# MCU.net
KiCad netlist of a schematic drawn in Altium Designer
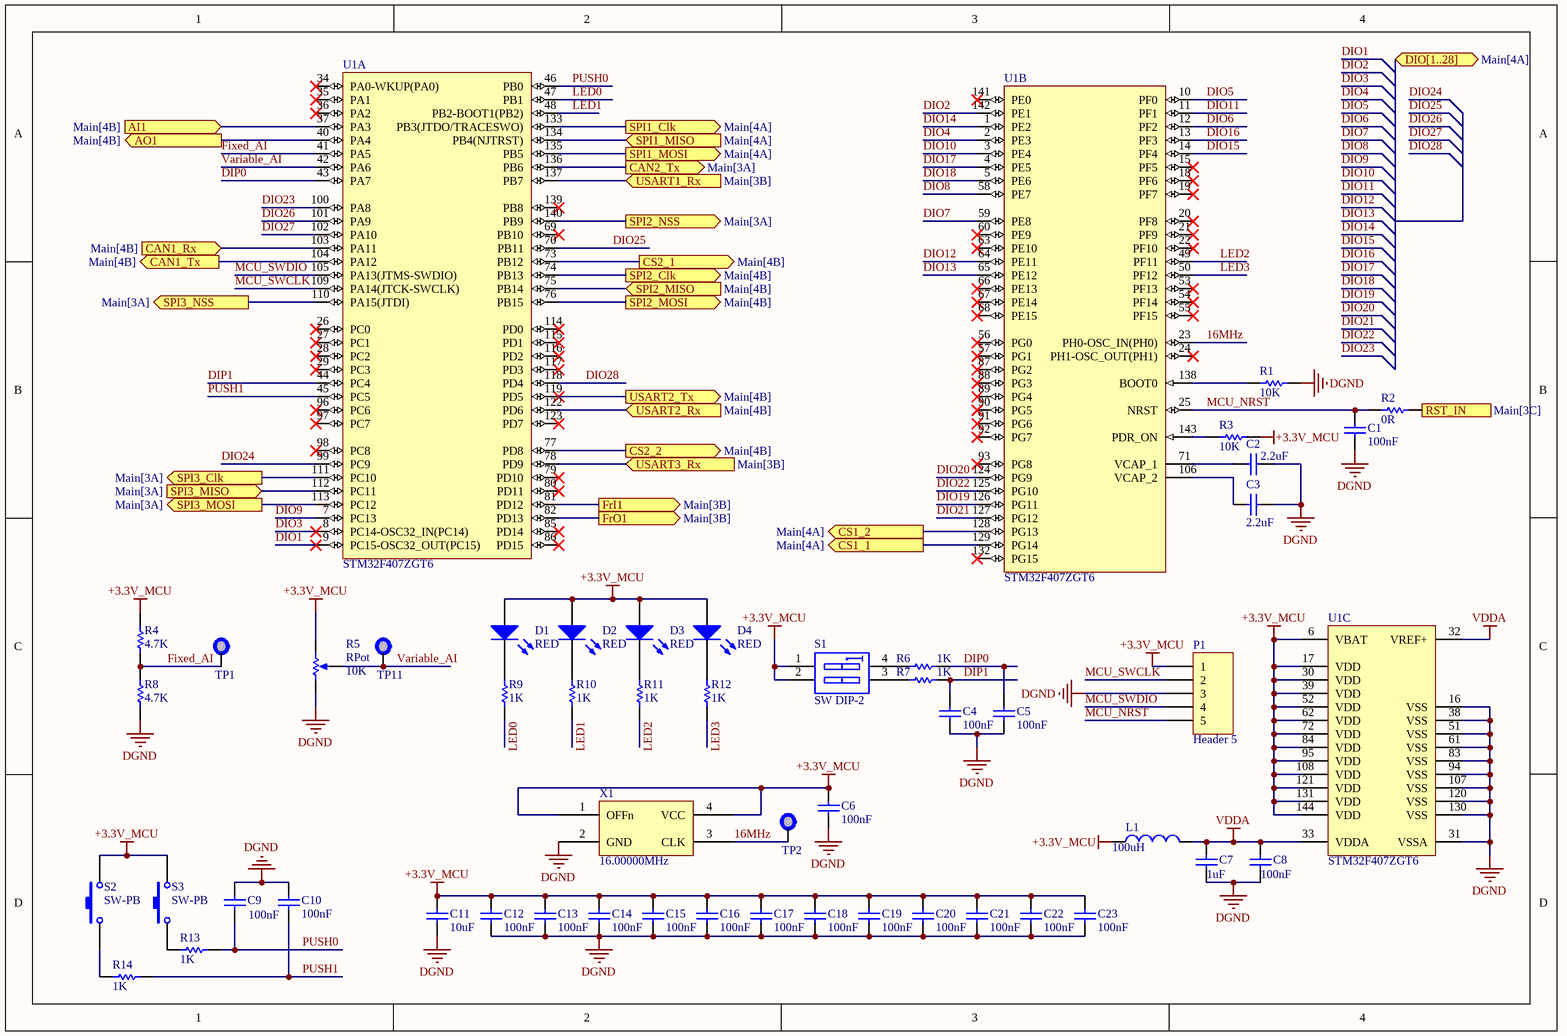
[diagram p0: MCU.SchDoc]

(export (version "E")
  (design (tool "Eeschema 10.0.6"))
  (components
    (comp (ref "C1")
      (value "100nF")
      (footprint "0603c")
      (description "LOW ESR")
      (fields (field (name "PUBLISHER") "Altium Limited"))
      (libsource (lib "Miscellaneous Devices") (part "Cap"))
    )
    (comp (ref "C2")
      (value "2.2uF")
      (footprint "0805C")
      (description "LOW ESR")
      (fields (field (name "PUBLISHER") "Altium Limited"))
      (libsource (lib "Miscellaneous Devices") (part "Cap"))
    )
    (comp (ref "C3")
      (value "2.2uF")
      (footprint "0805C")
      (description "LOW ESR")
      (fields (field (name "PUBLISHER") "Altium Limited"))
      (libsource (lib "Miscellaneous Devices") (part "Cap"))
    )
    (comp (ref "C4")
      (value "100nF")
      (footprint "0603c")
      (description "LOW ESR")
      (fields (field (name "PUBLISHER") "Altium Limited"))
      (libsource (lib "Miscellaneous Devices") (part "Cap"))
    )
    (comp (ref "C5")
      (value "100nF")
      (footprint "0603c")
      (description "LOW ESR")
      (fields (field (name "PUBLISHER") "Altium Limited"))
      (libsource (lib "Miscellaneous Devices") (part "Cap"))
    )
    (comp (ref "C6")
      (value "100nF")
      (footprint "0603C")
      (description "LOW ESR")
      (fields (field (name "PUBLISHER") "Altium Limited"))
      (libsource (lib "Miscellaneous Devices") (part "Cap"))
    )
    (comp (ref "C7")
      (value "1uF")
      (footprint "0805C")
      (description "LOW ESR")
      (fields (field (name "PUBLISHER") "Altium Limited"))
      (libsource (lib "Miscellaneous Devices") (part "Cap"))
    )
    (comp (ref "C8")
      (value "100nF")
      (footprint "0603C")
      (description "LOW ESR")
      (fields (field (name "PUBLISHER") "Altium Limited"))
      (libsource (lib "Miscellaneous Devices") (part "Cap"))
    )
    (comp (ref "C9")
      (value "100nF")
      (footprint "0603c")
      (description "LOW ESR")
      (fields (field (name "PUBLISHER") "Altium Limited"))
      (libsource (lib "Miscellaneous Devices") (part "Cap"))
    )
    (comp (ref "C10")
      (value "100nF")
      (footprint "0603c")
      (description "LOW ESR")
      (fields (field (name "PUBLISHER") "Altium Limited"))
      (libsource (lib "Miscellaneous Devices") (part "Cap"))
    )
    (comp (ref "C11")
      (value "10uF")
      (footprint "1206C")
      (description "LOW ESR")
      (fields (field (name "Comment") "10uf/50V") (field (name "PUBLISHER") "Altium Limited"))
      (libsource (lib "Miscellaneous Devices") (part "Cap"))
    )
    (comp (ref "C12")
      (value "100nF")
      (footprint "0603c")
      (description "LOW ESR")
      (fields (field (name "PUBLISHER") "Altium Limited"))
      (libsource (lib "Miscellaneous Devices") (part "Cap"))
    )
    (comp (ref "C13")
      (value "100nF")
      (footprint "0603c")
      (description "LOW ESR")
      (fields (field (name "PUBLISHER") "Altium Limited"))
      (libsource (lib "Miscellaneous Devices") (part "Cap"))
    )
    (comp (ref "C14")
      (value "100nF")
      (footprint "0603c")
      (description "LOW ESR")
      (fields (field (name "PUBLISHER") "Altium Limited"))
      (libsource (lib "Miscellaneous Devices") (part "Cap"))
    )
    (comp (ref "C15")
      (value "100nF")
      (footprint "0603c")
      (description "LOW ESR")
      (fields (field (name "PUBLISHER") "Altium Limited"))
      (libsource (lib "Miscellaneous Devices") (part "Cap"))
    )
    (comp (ref "C16")
      (value "100nF")
      (footprint "0603c")
      (description "LOW ESR")
      (fields (field (name "PUBLISHER") "Altium Limited"))
      (libsource (lib "Miscellaneous Devices") (part "Cap"))
    )
    (comp (ref "C17")
      (value "100nF")
      (footprint "0603c")
      (description "LOW ESR")
      (fields (field (name "PUBLISHER") "Altium Limited"))
      (libsource (lib "Miscellaneous Devices") (part "Cap"))
    )
    (comp (ref "C18")
      (value "100nF")
      (footprint "0603c")
      (description "LOW ESR")
      (fields (field (name "PUBLISHER") "Altium Limited"))
      (libsource (lib "Miscellaneous Devices") (part "Cap"))
    )
    (comp (ref "C19")
      (value "100nF")
      (footprint "0603c")
      (description "LOW ESR")
      (fields (field (name "PUBLISHER") "Altium Limited"))
      (libsource (lib "Miscellaneous Devices") (part "Cap"))
    )
    (comp (ref "C20")
      (value "100nF")
      (footprint "0603c")
      (description "LOW ESR")
      (fields (field (name "PUBLISHER") "Altium Limited"))
      (libsource (lib "Miscellaneous Devices") (part "Cap"))
    )
    (comp (ref "C21")
      (value "100nF")
      (footprint "0603c")
      (description "LOW ESR")
      (fields (field (name "PUBLISHER") "Altium Limited"))
      (libsource (lib "Miscellaneous Devices") (part "Cap"))
    )
    (comp (ref "C22")
      (value "100nF")
      (footprint "0603c")
      (description "LOW ESR")
      (fields (field (name "PUBLISHER") "Altium Limited"))
      (libsource (lib "Miscellaneous Devices") (part "Cap"))
    )
    (comp (ref "C23")
      (value "100nF")
      (footprint "0603c")
      (description "LOW ESR")
      (fields (field (name "PUBLISHER") "Altium Limited"))
      (libsource (lib "Miscellaneous Devices") (part "Cap"))
    )
    (comp (ref "D1")
      (value "RED")
      (footprint "0805LED")
      (fields (field (name "PUBLISHER") "Altium Limited"))
      (libsource (lib "Miscellaneous Devices") (part "LED0"))
    )
    (comp (ref "D2")
      (value "RED")
      (footprint "0805LED")
      (fields (field (name "PUBLISHER") "Altium Limited"))
      (libsource (lib "Miscellaneous Devices") (part "LED0"))
    )
    (comp (ref "D3")
      (value "RED")
      (footprint "0805LED")
      (fields (field (name "PUBLISHER") "Altium Limited"))
      (libsource (lib "Miscellaneous Devices") (part "LED0"))
    )
    (comp (ref "D4")
      (value "RED")
      (footprint "0805LED")
      (fields (field (name "PUBLISHER") "Altium Limited"))
      (libsource (lib "Miscellaneous Devices") (part "LED0"))
    )
    (comp (ref "L1")
      (value "100uH")
      (footprint "0805FB")
      (description "Inductor")
      (fields (field (name "PUBLISHER") "Altium Limited"))
      (libsource (lib "Miscellaneous Devices") (part "Inductor"))
    )
    (comp (ref "P1")
      (value "Header 5")
      (footprint "HDR1X5")
      (description "Header, 5-Pin")
      (fields (field (name "PUBLISHER") "Altium Limited"))
      (libsource (lib "Miscellaneous Connectors") (part "Header 5"))
    )
    (comp (ref "R1")
      (value "10K")
      (footprint "0805")
      (description "Resistor")
      (fields (field (name "PUBLISHER") "Altium Limited"))
      (libsource (lib "Miscellaneous Devices") (part "Res1"))
    )
    (comp (ref "R2")
      (value "0R")
      (footprint "0805")
      (description "Resistor")
      (fields (field (name "PUBLISHER") "Altium Limited"))
      (libsource (lib "Miscellaneous Devices") (part "Res1"))
    )
    (comp (ref "R3")
      (value "10K")
      (footprint "0805")
      (description "Resistor")
      (fields (field (name "PUBLISHER") "Altium Limited"))
      (libsource (lib "Miscellaneous Devices") (part "Res1"))
    )
    (comp (ref "R4")
      (value "4.7K")
      (footprint "0805")
      (description "Resistor")
      (fields (field (name "PUBLISHER") "Altium Limited"))
      (libsource (lib "Miscellaneous Devices") (part "Res1"))
    )
    (comp (ref "R5")
      (value "RPot")
      (footprint "POT-MULTITURN")
      (description "MultiTurn")
      (fields (field (name "ALTIUM_VALUE") "10K") (field (name "PUBLISHER") "Altium Limited"))
      (libsource (lib "Miscellaneous Devices") (part "RPot"))
    )
    (comp (ref "R6")
      (value "1K")
      (footprint "0805")
      (description "Resistor")
      (fields (field (name "PUBLISHER") "Altium Limited"))
      (libsource (lib "Miscellaneous Devices") (part "Res1"))
    )
    (comp (ref "R7")
      (value "1K")
      (footprint "0805")
      (description "Resistor")
      (fields (field (name "PUBLISHER") "Altium Limited"))
      (libsource (lib "Miscellaneous Devices") (part "Res1"))
    )
    (comp (ref "R8")
      (value "4.7K")
      (footprint "0805")
      (description "Resistor")
      (fields (field (name "PUBLISHER") "Altium Limited"))
      (libsource (lib "Miscellaneous Devices") (part "Res1"))
    )
    (comp (ref "R9")
      (value "1K")
      (footprint "0805")
      (description "Resistor")
      (fields (field (name "PUBLISHER") "Altium Limited"))
      (libsource (lib "Miscellaneous Devices") (part "Res1"))
    )
    (comp (ref "R10")
      (value "1K")
      (footprint "0805")
      (description "Resistor")
      (fields (field (name "PUBLISHER") "Altium Limited"))
      (libsource (lib "Miscellaneous Devices") (part "Res1"))
    )
    (comp (ref "R11")
      (value "1K")
      (footprint "0805")
      (description "Resistor")
      (fields (field (name "PUBLISHER") "Altium Limited"))
      (libsource (lib "Miscellaneous Devices") (part "Res1"))
    )
    (comp (ref "R12")
      (value "1K")
      (footprint "0805")
      (description "Resistor")
      (fields (field (name "PUBLISHER") "Altium Limited"))
      (libsource (lib "Miscellaneous Devices") (part "Res1"))
    )
    (comp (ref "R13")
      (value "1K")
      (footprint "0805")
      (description "Resistor")
      (fields (field (name "PUBLISHER") "Altium Limited"))
      (libsource (lib "Miscellaneous Devices") (part "Res1"))
    )
    (comp (ref "R14")
      (value "1K")
      (footprint "0805")
      (description "Resistor")
      (fields (field (name "PUBLISHER") "Altium Limited"))
      (libsource (lib "Miscellaneous Devices") (part "Res1"))
    )
    (comp (ref "S1")
      (value "SW DIP-2")
      (footprint "DIP-4")
      (description "DIP Switch, 2 Position, SPST")
      (fields (field (name "PUBLISHER") "Altium Limited"))
      (libsource (lib "Miscellaneous Devices") (part "SW DIP-2"))
    )
    (comp (ref "S2")
      (value "SW-PB")
      (footprint "PUSHBUTTON-SMD")
      (description "Switch")
      (fields (field (name "PUBLISHER") "Altium Limited"))
      (libsource (lib "Miscellaneous Devices") (part "SW-PB"))
    )
    (comp (ref "S3")
      (value "SW-PB")
      (footprint "PUSHBUTTON-SMD")
      (description "Switch")
      (fields (field (name "PUBLISHER") "Altium Limited"))
      (libsource (lib "Miscellaneous Devices") (part "SW-PB"))
    )
    (comp (ref "TP1") (value "TestPoint") (footprint "TP") (libsource (lib "SchlibV0.1") (part "TestPoint")))
    (comp (ref "TP2") (value "TestPoint") (footprint "TP") (libsource (lib "SchlibV0.1") (part "TestPoint")))
    (comp (ref "TP11") (value "TestPoint") (footprint "TP") (libsource (lib "SchlibV0.1") (part "TestPoint")))
    (comp (ref "U1")
      (value "STM32F407ZGT6")
      (footprint "STM-LQFP144_N")
      (fields (field (name "MANUFACTURER") "STMicroelectronics"))
      (libsource (lib "STMicroelectronics STM32 F4") (part "STM32F407ZGT6"))
    )
    (comp (ref "X1")
      (value "16.00000MHz")
      (footprint "OSC-SMT")
      (fields (field (name "Comment") "SG-8018CB 16.000000 MHZ TJHPA"))
      (libsource (lib "TMS320F2812-PGF") (part "Oscillator"))
    )
  )
  (nets
    (net (code "1") (name "+3.3V_MCU") (class "Default")
      (node (ref "C11") (pin "2") (pinfunction "2_2") (pintype "passive"))
      (node (ref "C12") (pin "1") (pinfunction "1_1") (pintype "passive"))
      (node (ref "C13") (pin "1") (pinfunction "1_1") (pintype "passive"))
      (node (ref "C14") (pin "1") (pinfunction "1_1") (pintype "passive"))
      (node (ref "C15") (pin "1") (pinfunction "1_1") (pintype "passive"))
      (node (ref "C16") (pin "1") (pinfunction "1_1") (pintype "passive"))
      (node (ref "C17") (pin "1") (pinfunction "1_1") (pintype "passive"))
      (node (ref "C18") (pin "1") (pinfunction "1_1") (pintype "passive"))
      (node (ref "C19") (pin "1") (pinfunction "1_1") (pintype "passive"))
      (node (ref "C20") (pin "1") (pinfunction "1_1") (pintype "passive"))
      (node (ref "C21") (pin "1") (pinfunction "1_1") (pintype "passive"))
      (node (ref "C22") (pin "1") (pinfunction "1_1") (pintype "passive"))
      (node (ref "C23") (pin "1") (pinfunction "1_1") (pintype "passive"))
      (node (ref "C6") (pin "1") (pinfunction "1_1") (pintype "passive"))
      (node (ref "D1") (pin "1") (pinfunction "A_1") (pintype "passive"))
      (node (ref "D2") (pin "1") (pinfunction "A_1") (pintype "passive"))
      (node (ref "D3") (pin "1") (pinfunction "A_1") (pintype "passive"))
      (node (ref "D4") (pin "1") (pinfunction "A_1") (pintype "passive"))
      (node (ref "L1") (pin "1") (pinfunction "1_1") (pintype "passive"))
      (node (ref "P1") (pin "1") (pinfunction "1_1") (pintype "passive"))
      (node (ref "R3") (pin "1") (pinfunction "1_1") (pintype "passive"))
      (node (ref "R4") (pin "2") (pinfunction "2_2") (pintype "passive"))
      (node (ref "R5") (pin "3") (pinfunction "BOT_3") (pintype "passive"))
      (node (ref "S1") (pin "1") (pinfunction "A1_1") (pintype "passive"))
      (node (ref "S1") (pin "2") (pinfunction "A2_2") (pintype "passive"))
      (node (ref "S2") (pin "2") (pinfunction "2_2") (pintype "passive"))
      (node (ref "S3") (pin "2") (pinfunction "2_2") (pintype "passive"))
      (node (ref "U1") (pin "108") (pinfunction "VDD_108") (pintype "power_in"))
      (node (ref "U1") (pin "121") (pinfunction "VDD_121") (pintype "power_in"))
      (node (ref "U1") (pin "131") (pinfunction "VDD_131") (pintype "power_in"))
      (node (ref "U1") (pin "144") (pinfunction "VDD_144") (pintype "power_in"))
      (node (ref "U1") (pin "17") (pinfunction "VDD_17") (pintype "power_in"))
      (node (ref "U1") (pin "30") (pinfunction "VDD_30") (pintype "power_in"))
      (node (ref "U1") (pin "39") (pinfunction "VDD_39") (pintype "power_in"))
      (node (ref "U1") (pin "52") (pinfunction "VDD_52") (pintype "power_in"))
      (node (ref "U1") (pin "6") (pinfunction "VBAT_6") (pintype "power_in"))
      (node (ref "U1") (pin "62") (pinfunction "VDD_62") (pintype "power_in"))
      (node (ref "U1") (pin "72") (pinfunction "VDD_72") (pintype "power_in"))
      (node (ref "U1") (pin "84") (pinfunction "VDD_84") (pintype "power_in"))
      (node (ref "U1") (pin "95") (pinfunction "VDD_95") (pintype "power_in"))
      (node (ref "X1") (pin "1") (pinfunction "OFFn_1") (pintype "passive"))
      (node (ref "X1") (pin "4") (pinfunction "VCC_4") (pintype "passive"))
    )
    (net (code "2") (name "/16MHz") (class "Default")
      (node (ref "TP2") (pin "1") (pintype "passive"))
      (node (ref "U1") (pin "23") (pinfunction "PH0-OSC_IN(PH0)_23") (pintype "bidirectional"))
      (node (ref "X1") (pin "3") (pinfunction "CLK_3") (pintype "passive"))
    )
    (net (code "3") (name "/AI1") (class "Default")
      (node (ref "U1") (pin "37") (pinfunction "PA3_37") (pintype "bidirectional"))
    )
    (net (code "4") (name "/AO1") (class "Default")
      (node (ref "U1") (pin "40") (pinfunction "PA4_40") (pintype "bidirectional"))
    )
    (net (code "5") (name "/CAN1_Rx") (class "Default")
      (node (ref "U1") (pin "103") (pinfunction "PA11_103") (pintype "bidirectional"))
    )
    (net (code "6") (name "/CAN1_Tx") (class "Default")
      (node (ref "U1") (pin "104") (pinfunction "PA12_104") (pintype "bidirectional"))
    )
    (net (code "7") (name "/CAN2_Tx") (class "Default")
      (node (ref "U1") (pin "136") (pinfunction "PB6_136") (pintype "bidirectional"))
    )
    (net (code "8") (name "/CS1_1") (class "Default")
      (node (ref "U1") (pin "129") (pinfunction "PG14_129") (pintype "bidirectional"))
    )
    (net (code "9") (name "/CS1_2") (class "Default")
      (node (ref "U1") (pin "128") (pinfunction "PG13_128") (pintype "bidirectional"))
    )
    (net (code "10") (name "/CS2_1") (class "Default")
      (node (ref "U1") (pin "73") (pinfunction "PB12_73") (pintype "bidirectional"))
    )
    (net (code "11") (name "/CS2_2") (class "Default")
      (node (ref "U1") (pin "77") (pinfunction "PD8_77") (pintype "bidirectional"))
    )
    (net (code "12") (name "/DIO1") (class "Default")
      (node (ref "U1") (pin "9") (pinfunction "PC15-OSC32_OUT(PC15)_9") (pintype "bidirectional+no_connect"))
    )
    (net (code "13") (name "/DIO2") (class "Default")
      (node (ref "U1") (pin "142") (pinfunction "PE1_142") (pintype "bidirectional"))
    )
    (net (code "14") (name "/DIO3") (class "Default")
      (node (ref "U1") (pin "8") (pinfunction "PC14-OSC32_IN(PC14)_8") (pintype "bidirectional+no_connect"))
    )
    (net (code "15") (name "/DIO4") (class "Default")
      (node (ref "U1") (pin "2") (pinfunction "PE3_2") (pintype "bidirectional"))
    )
    (net (code "16") (name "/DIO5") (class "Default")
      (node (ref "U1") (pin "10") (pinfunction "PF0_10") (pintype "bidirectional"))
    )
    (net (code "17") (name "/DIO6") (class "Default")
      (node (ref "U1") (pin "12") (pinfunction "PF2_12") (pintype "bidirectional"))
    )
    (net (code "18") (name "/DIO7") (class "Default")
      (node (ref "U1") (pin "59") (pinfunction "PE8_59") (pintype "bidirectional"))
    )
    (net (code "19") (name "/DIO8") (class "Default")
      (node (ref "U1") (pin "58") (pinfunction "PE7_58") (pintype "bidirectional"))
    )
    (net (code "20") (name "/DIO9") (class "Default")
      (node (ref "U1") (pin "7") (pinfunction "PC13_7") (pintype "bidirectional"))
    )
    (net (code "21") (name "/DIO10") (class "Default")
      (node (ref "U1") (pin "3") (pinfunction "PE4_3") (pintype "bidirectional"))
    )
    (net (code "22") (name "/DIO11") (class "Default")
      (node (ref "U1") (pin "11") (pinfunction "PF1_11") (pintype "bidirectional"))
    )
    (net (code "23") (name "/DIO12") (class "Default")
      (node (ref "U1") (pin "64") (pinfunction "PE11_64") (pintype "bidirectional"))
    )
    (net (code "24") (name "/DIO13") (class "Default")
      (node (ref "U1") (pin "65") (pinfunction "PE12_65") (pintype "bidirectional"))
    )
    (net (code "25") (name "/DIO14") (class "Default")
      (node (ref "U1") (pin "1") (pinfunction "PE2_1") (pintype "bidirectional"))
    )
    (net (code "26") (name "/DIO15") (class "Default")
      (node (ref "U1") (pin "14") (pinfunction "PF4_14") (pintype "bidirectional"))
    )
    (net (code "27") (name "/DIO16") (class "Default")
      (node (ref "U1") (pin "13") (pinfunction "PF3_13") (pintype "bidirectional"))
    )
    (net (code "28") (name "/DIO17") (class "Default")
      (node (ref "U1") (pin "4") (pinfunction "PE5_4") (pintype "bidirectional"))
    )
    (net (code "29") (name "/DIO18") (class "Default")
      (node (ref "U1") (pin "5") (pinfunction "PE6_5") (pintype "bidirectional"))
    )
    (net (code "30") (name "/DIO19") (class "Default")
      (node (ref "U1") (pin "126") (pinfunction "PG11_126") (pintype "bidirectional"))
    )
    (net (code "31") (name "/DIO20") (class "Default")
      (node (ref "U1") (pin "124") (pinfunction "PG9_124") (pintype "bidirectional"))
    )
    (net (code "32") (name "/DIO21") (class "Default")
      (node (ref "U1") (pin "127") (pinfunction "PG12_127") (pintype "bidirectional"))
    )
    (net (code "33") (name "/DIO22") (class "Default")
      (node (ref "U1") (pin "125") (pinfunction "PG10_125") (pintype "bidirectional"))
    )
    (net (code "34") (name "/DIO23") (class "Default")
      (node (ref "U1") (pin "100") (pinfunction "PA8_100") (pintype "bidirectional"))
    )
    (net (code "35") (name "/DIO24") (class "Default")
      (node (ref "U1") (pin "99") (pinfunction "PC9_99") (pintype "bidirectional"))
    )
    (net (code "36") (name "/DIO25") (class "Default")
      (node (ref "U1") (pin "70") (pinfunction "PB11_70") (pintype "bidirectional"))
    )
    (net (code "37") (name "/DIO26") (class "Default")
      (node (ref "U1") (pin "101") (pinfunction "PA9_101") (pintype "bidirectional"))
    )
    (net (code "38") (name "/DIO27") (class "Default")
      (node (ref "U1") (pin "102") (pinfunction "PA10_102") (pintype "bidirectional"))
    )
    (net (code "39") (name "/DIO28") (class "Default")
      (node (ref "U1") (pin "118") (pinfunction "PD4_118") (pintype "bidirectional"))
    )
    (net (code "41") (name "/DIP0") (class "Default")
      (node (ref "C5") (pin "1") (pinfunction "1_1") (pintype "passive"))
      (node (ref "R6") (pin "2") (pinfunction "2_2") (pintype "passive"))
      (node (ref "U1") (pin "43") (pinfunction "PA7_43") (pintype "bidirectional"))
    )
    (net (code "42") (name "/DIP1") (class "Default")
      (node (ref "C4") (pin "1") (pinfunction "1_1") (pintype "passive"))
      (node (ref "R7") (pin "2") (pinfunction "2_2") (pintype "passive"))
      (node (ref "U1") (pin "44") (pinfunction "PC4_44") (pintype "bidirectional"))
    )
    (net (code "43") (name "/Fixed_AI") (class "Default")
      (node (ref "R4") (pin "1") (pinfunction "1_1") (pintype "passive"))
      (node (ref "R8") (pin "2") (pinfunction "2_2") (pintype "passive"))
      (node (ref "TP1") (pin "1") (pintype "passive"))
      (node (ref "U1") (pin "41") (pinfunction "PA5_41") (pintype "bidirectional"))
    )
    (net (code "44") (name "/FrI1") (class "Default")
      (node (ref "U1") (pin "81") (pinfunction "PD12_81") (pintype "bidirectional"))
    )
    (net (code "45") (name "/FrO1") (class "Default")
      (node (ref "U1") (pin "82") (pinfunction "PD13_82") (pintype "bidirectional"))
    )
    (net (code "46") (name "/LED0") (class "Default")
      (node (ref "R9") (pin "1") (pinfunction "1_1") (pintype "passive"))
      (node (ref "U1") (pin "47") (pinfunction "PB1_47") (pintype "bidirectional"))
    )
    (net (code "47") (name "/LED1") (class "Default")
      (node (ref "R10") (pin "1") (pinfunction "1_1") (pintype "passive"))
      (node (ref "U1") (pin "48") (pinfunction "PB2-BOOT1(PB2)_48") (pintype "bidirectional"))
    )
    (net (code "48") (name "/LED2") (class "Default")
      (node (ref "R11") (pin "1") (pinfunction "1_1") (pintype "passive"))
      (node (ref "U1") (pin "49") (pinfunction "PF11_49") (pintype "bidirectional"))
    )
    (net (code "49") (name "/LED3") (class "Default")
      (node (ref "R12") (pin "1") (pinfunction "1_1") (pintype "passive"))
      (node (ref "U1") (pin "50") (pinfunction "PF12_50") (pintype "bidirectional"))
    )
    (net (code "50") (name "/MCU_NRST") (class "Default")
      (node (ref "C1") (pin "1") (pinfunction "1_1") (pintype "passive"))
      (node (ref "P1") (pin "5") (pinfunction "5_5") (pintype "passive"))
      (node (ref "R2") (pin "2") (pinfunction "2_2") (pintype "passive"))
      (node (ref "U1") (pin "25") (pinfunction "NRST_25") (pintype "bidirectional"))
    )
    (net (code "51") (name "/MCU_SWCLK") (class "Default")
      (node (ref "P1") (pin "2") (pinfunction "2_2") (pintype "passive"))
      (node (ref "U1") (pin "109") (pinfunction "PA14(JTCK-SWCLK)_109") (pintype "bidirectional"))
    )
    (net (code "52") (name "/MCU_SWDIO") (class "Default")
      (node (ref "P1") (pin "4") (pinfunction "4_4") (pintype "passive"))
      (node (ref "U1") (pin "105") (pinfunction "PA13(JTMS-SWDIO)_105") (pintype "bidirectional"))
    )
    (net (code "53") (name "/PUSH0") (class "Default")
      (node (ref "C9") (pin "2") (pinfunction "2_2") (pintype "passive"))
      (node (ref "R13") (pin "2") (pinfunction "2_2") (pintype "passive"))
      (node (ref "U1") (pin "46") (pinfunction "PB0_46") (pintype "bidirectional"))
    )
    (net (code "54") (name "/PUSH1") (class "Default")
      (node (ref "C10") (pin "2") (pinfunction "2_2") (pintype "passive"))
      (node (ref "R14") (pin "1") (pinfunction "1_1") (pintype "passive"))
      (node (ref "U1") (pin "45") (pinfunction "PC5_45") (pintype "bidirectional"))
    )
    (net (code "55") (name "/RST_IN") (class "Default")
      (node (ref "R2") (pin "1") (pinfunction "1_1") (pintype "passive"))
    )
    (net (code "56") (name "/SPI1_Clk") (class "Default")
      (node (ref "U1") (pin "133") (pinfunction "PB3(JTDO/TRACESWO)_133") (pintype "bidirectional"))
    )
    (net (code "57") (name "/SPI1_MISO") (class "Default")
      (node (ref "U1") (pin "134") (pinfunction "PB4(NJTRST)_134") (pintype "bidirectional"))
    )
    (net (code "58") (name "/SPI1_MOSI") (class "Default")
      (node (ref "U1") (pin "135") (pinfunction "PB5_135") (pintype "bidirectional"))
    )
    (net (code "59") (name "/SPI2_Clk") (class "Default")
      (node (ref "U1") (pin "74") (pinfunction "PB13_74") (pintype "bidirectional"))
    )
    (net (code "60") (name "/SPI2_MISO") (class "Default")
      (node (ref "U1") (pin "75") (pinfunction "PB14_75") (pintype "bidirectional"))
    )
    (net (code "61") (name "/SPI2_MOSI") (class "Default")
      (node (ref "U1") (pin "76") (pinfunction "PB15_76") (pintype "bidirectional"))
    )
    (net (code "62") (name "/SPI2_NSS") (class "Default")
      (node (ref "U1") (pin "140") (pinfunction "PB9_140") (pintype "bidirectional"))
    )
    (net (code "63") (name "/SPI3_Clk") (class "Default")
      (node (ref "U1") (pin "111") (pinfunction "PC10_111") (pintype "bidirectional"))
    )
    (net (code "64") (name "/SPI3_MISO") (class "Default")
      (node (ref "U1") (pin "112") (pinfunction "PC11_112") (pintype "bidirectional"))
    )
    (net (code "65") (name "/SPI3_MOSI") (class "Default")
      (node (ref "U1") (pin "113") (pinfunction "PC12_113") (pintype "bidirectional"))
    )
    (net (code "66") (name "/SPI3_NSS") (class "Default")
      (node (ref "U1") (pin "110") (pinfunction "PA15(JTDI)_110") (pintype "bidirectional"))
    )
    (net (code "67") (name "/USART1_Rx") (class "Default")
      (node (ref "U1") (pin "137") (pinfunction "PB7_137") (pintype "bidirectional"))
    )
    (net (code "68") (name "/USART2_Rx") (class "Default")
      (node (ref "U1") (pin "122") (pinfunction "PD6_122") (pintype "bidirectional"))
    )
    (net (code "69") (name "/USART2_Tx") (class "Default")
      (node (ref "U1") (pin "119") (pinfunction "PD5_119") (pintype "bidirectional+no_connect"))
    )
    (net (code "70") (name "/USART3_Rx") (class "Default")
      (node (ref "U1") (pin "78") (pinfunction "PD9_78") (pintype "bidirectional"))
    )
    (net (code "71") (name "/Variable_AI") (class "Default")
      (node (ref "R5") (pin "2") (pinfunction "TAP_2") (pintype "passive"))
      (node (ref "TP11") (pin "1") (pintype "passive"))
      (node (ref "U1") (pin "42") (pinfunction "PA6_42") (pintype "bidirectional"))
    )
    (net (code "72") (name "DGND") (class "Default")
      (node (ref "C1") (pin "2") (pinfunction "2_2") (pintype "passive"))
      (node (ref "C10") (pin "1") (pinfunction "1_1") (pintype "passive"))
      (node (ref "C11") (pin "1") (pinfunction "1_1") (pintype "passive"))
      (node (ref "C12") (pin "2") (pinfunction "2_2") (pintype "passive"))
      (node (ref "C13") (pin "2") (pinfunction "2_2") (pintype "passive"))
      (node (ref "C14") (pin "2") (pinfunction "2_2") (pintype "passive"))
      (node (ref "C15") (pin "2") (pinfunction "2_2") (pintype "passive"))
      (node (ref "C16") (pin "2") (pinfunction "2_2") (pintype "passive"))
      (node (ref "C17") (pin "2") (pinfunction "2_2") (pintype "passive"))
      (node (ref "C18") (pin "2") (pinfunction "2_2") (pintype "passive"))
      (node (ref "C19") (pin "2") (pinfunction "2_2") (pintype "passive"))
      (node (ref "C2") (pin "2") (pinfunction "2_2") (pintype "passive"))
      (node (ref "C20") (pin "2") (pinfunction "2_2") (pintype "passive"))
      (node (ref "C21") (pin "2") (pinfunction "2_2") (pintype "passive"))
      (node (ref "C22") (pin "2") (pinfunction "2_2") (pintype "passive"))
      (node (ref "C23") (pin "2") (pinfunction "2_2") (pintype "passive"))
      (node (ref "C3") (pin "2") (pinfunction "2_2") (pintype "passive"))
      (node (ref "C4") (pin "2") (pinfunction "2_2") (pintype "passive"))
      (node (ref "C5") (pin "2") (pinfunction "2_2") (pintype "passive"))
      (node (ref "C6") (pin "2") (pinfunction "2_2") (pintype "passive"))
      (node (ref "C7") (pin "1") (pinfunction "1_1") (pintype "passive"))
      (node (ref "C8") (pin "1") (pinfunction "1_1") (pintype "passive"))
      (node (ref "C9") (pin "1") (pinfunction "1_1") (pintype "passive"))
      (node (ref "P1") (pin "3") (pinfunction "3_3") (pintype "passive"))
      (node (ref "R1") (pin "1") (pinfunction "1_1") (pintype "passive"))
      (node (ref "R5") (pin "1") (pinfunction "TOP_1") (pintype "passive"))
      (node (ref "R8") (pin "1") (pinfunction "1_1") (pintype "passive"))
      (node (ref "U1") (pin "107") (pinfunction "VSS_107") (pintype "power_in"))
      (node (ref "U1") (pin "120") (pinfunction "VSS_120") (pintype "power_in"))
      (node (ref "U1") (pin "130") (pinfunction "VSS_130") (pintype "power_in"))
      (node (ref "U1") (pin "16") (pinfunction "VSS_16") (pintype "power_in"))
      (node (ref "U1") (pin "31") (pinfunction "VSSA_31") (pintype "power_in"))
      (node (ref "U1") (pin "38") (pinfunction "VSS_38") (pintype "power_in"))
      (node (ref "U1") (pin "51") (pinfunction "VSS_51") (pintype "power_in"))
      (node (ref "U1") (pin "61") (pinfunction "VSS_61") (pintype "power_in"))
      (node (ref "U1") (pin "83") (pinfunction "VSS_83") (pintype "power_in"))
      (node (ref "U1") (pin "94") (pinfunction "VSS_94") (pintype "power_in"))
      (node (ref "X1") (pin "2") (pinfunction "GND_2") (pintype "passive"))
    )
    (net (code "73") (name "Net-(D1-K)") (class "Default")
      (node (ref "D1") (pin "2") (pinfunction "K_2") (pintype "passive"))
      (node (ref "R9") (pin "2") (pinfunction "2_2") (pintype "passive"))
    )
    (net (code "74") (name "Net-(D2-K)") (class "Default")
      (node (ref "D2") (pin "2") (pinfunction "K_2") (pintype "passive"))
      (node (ref "R10") (pin "2") (pinfunction "2_2") (pintype "passive"))
    )
    (net (code "75") (name "Net-(D3-K)") (class "Default")
      (node (ref "D3") (pin "2") (pinfunction "K_2") (pintype "passive"))
      (node (ref "R11") (pin "2") (pinfunction "2_2") (pintype "passive"))
    )
    (net (code "76") (name "Net-(D4-K)") (class "Default")
      (node (ref "D4") (pin "2") (pinfunction "K_2") (pintype "passive"))
      (node (ref "R12") (pin "2") (pinfunction "2_2") (pintype "passive"))
    )
    (net (code "77") (name "Net-(R13-Pad1)") (class "Default")
      (node (ref "R13") (pin "1") (pinfunction "1_1") (pintype "passive"))
      (node (ref "S3") (pin "1") (pinfunction "1_1") (pintype "passive"))
    )
    (net (code "78") (name "Net-(R14-Pad2)") (class "Default")
      (node (ref "R14") (pin "2") (pinfunction "2_2") (pintype "passive"))
      (node (ref "S2") (pin "1") (pinfunction "1_1") (pintype "passive"))
    )
    (net (code "79") (name "Net-(S1-B1)") (class "Default")
      (node (ref "R6") (pin "1") (pinfunction "1_1") (pintype "passive"))
      (node (ref "S1") (pin "4") (pinfunction "B1_4") (pintype "passive"))
    )
    (net (code "80") (name "Net-(S1-B2)") (class "Default")
      (node (ref "R7") (pin "1") (pinfunction "1_1") (pintype "passive"))
      (node (ref "S1") (pin "3") (pinfunction "B2_3") (pintype "passive"))
    )
    (net (code "81") (name "Net-(U1B-BOOT0)") (class "Default")
      (node (ref "R1") (pin "2") (pinfunction "2_2") (pintype "passive"))
      (node (ref "U1") (pin "138") (pinfunction "BOOT0_138") (pintype "input"))
    )
    (net (code "82") (name "Net-(U1B-PDR_ON)") (class "Default")
      (node (ref "R3") (pin "2") (pinfunction "2_2") (pintype "passive"))
      (node (ref "U1") (pin "143") (pinfunction "PDR_ON_143") (pintype "input"))
    )
    (net (code "83") (name "Net-(U1B-VCAP_1)") (class "Default")
      (node (ref "C2") (pin "1") (pinfunction "1_1") (pintype "passive"))
      (node (ref "U1") (pin "71") (pinfunction "VCAP_1_71") (pintype "power_in"))
    )
    (net (code "84") (name "Net-(U1B-VCAP_2)") (class "Default")
      (node (ref "C3") (pin "1") (pinfunction "1_1") (pintype "passive"))
      (node (ref "U1") (pin "106") (pinfunction "VCAP_2_106") (pintype "power_in"))
    )
    (net (code "85") (name "VDDA") (class "Default")
      (node (ref "C7") (pin "2") (pinfunction "2_2") (pintype "passive"))
      (node (ref "C8") (pin "2") (pinfunction "2_2") (pintype "passive"))
      (node (ref "L1") (pin "2") (pinfunction "2_2") (pintype "passive"))
      (node (ref "U1") (pin "32") (pinfunction "VREF+_32") (pintype "power_in"))
      (node (ref "U1") (pin "33") (pinfunction "VDDA_33") (pintype "power_in"))
    )
    (net (code "86") (name "unconnected-(U1A-PA0-WKUP(PA0)-Pad34)") (class "Default")
      (node (ref "U1") (pin "34") (pinfunction "PA0-WKUP(PA0)_34") (pintype "bidirectional+no_connect"))
    )
    (net (code "87") (name "unconnected-(U1A-PA1-Pad35)") (class "Default")
      (node (ref "U1") (pin "35") (pinfunction "PA1_35") (pintype "bidirectional+no_connect"))
    )
    (net (code "88") (name "unconnected-(U1A-PA2-Pad36)") (class "Default")
      (node (ref "U1") (pin "36") (pinfunction "PA2_36") (pintype "bidirectional+no_connect"))
    )
    (net (code "89") (name "unconnected-(U1A-PB8-Pad139)") (class "Default")
      (node (ref "U1") (pin "139") (pinfunction "PB8_139") (pintype "bidirectional+no_connect"))
    )
    (net (code "90") (name "unconnected-(U1A-PB10-Pad69)") (class "Default")
      (node (ref "U1") (pin "69") (pinfunction "PB10_69") (pintype "bidirectional+no_connect"))
    )
    (net (code "91") (name "unconnected-(U1A-PC0-Pad26)") (class "Default")
      (node (ref "U1") (pin "26") (pinfunction "PC0_26") (pintype "bidirectional+no_connect"))
    )
    (net (code "92") (name "unconnected-(U1A-PC1-Pad27)") (class "Default")
      (node (ref "U1") (pin "27") (pinfunction "PC1_27") (pintype "bidirectional+no_connect"))
    )
    (net (code "93") (name "unconnected-(U1A-PC2-Pad28)") (class "Default")
      (node (ref "U1") (pin "28") (pinfunction "PC2_28") (pintype "bidirectional+no_connect"))
    )
    (net (code "94") (name "unconnected-(U1A-PC3-Pad29)") (class "Default")
      (node (ref "U1") (pin "29") (pinfunction "PC3_29") (pintype "bidirectional+no_connect"))
    )
    (net (code "95") (name "unconnected-(U1A-PC6-Pad96)") (class "Default")
      (node (ref "U1") (pin "96") (pinfunction "PC6_96") (pintype "bidirectional+no_connect"))
    )
    (net (code "96") (name "unconnected-(U1A-PC7-Pad97)") (class "Default")
      (node (ref "U1") (pin "97") (pinfunction "PC7_97") (pintype "bidirectional+no_connect"))
    )
    (net (code "97") (name "unconnected-(U1A-PC8-Pad98)") (class "Default")
      (node (ref "U1") (pin "98") (pinfunction "PC8_98") (pintype "bidirectional+no_connect"))
    )
    (net (code "98") (name "unconnected-(U1A-PD0-Pad114)") (class "Default")
      (node (ref "U1") (pin "114") (pinfunction "PD0_114") (pintype "bidirectional+no_connect"))
    )
    (net (code "99") (name "unconnected-(U1A-PD1-Pad115)") (class "Default")
      (node (ref "U1") (pin "115") (pinfunction "PD1_115") (pintype "bidirectional+no_connect"))
    )
    (net (code "100") (name "unconnected-(U1A-PD2-Pad116)") (class "Default")
      (node (ref "U1") (pin "116") (pinfunction "PD2_116") (pintype "bidirectional+no_connect"))
    )
    (net (code "101") (name "unconnected-(U1A-PD3-Pad117)") (class "Default")
      (node (ref "U1") (pin "117") (pinfunction "PD3_117") (pintype "bidirectional+no_connect"))
    )
    (net (code "102") (name "unconnected-(U1A-PD7-Pad123)") (class "Default")
      (node (ref "U1") (pin "123") (pinfunction "PD7_123") (pintype "bidirectional+no_connect"))
    )
    (net (code "103") (name "unconnected-(U1A-PD10-Pad79)") (class "Default")
      (node (ref "U1") (pin "79") (pinfunction "PD10_79") (pintype "bidirectional+no_connect"))
    )
    (net (code "104") (name "unconnected-(U1A-PD11-Pad80)") (class "Default")
      (node (ref "U1") (pin "80") (pinfunction "PD11_80") (pintype "bidirectional+no_connect"))
    )
    (net (code "105") (name "unconnected-(U1A-PD14-Pad85)") (class "Default")
      (node (ref "U1") (pin "85") (pinfunction "PD14_85") (pintype "bidirectional+no_connect"))
    )
    (net (code "106") (name "unconnected-(U1A-PD15-Pad86)") (class "Default")
      (node (ref "U1") (pin "86") (pinfunction "PD15_86") (pintype "bidirectional+no_connect"))
    )
    (net (code "107") (name "unconnected-(U1B-PE0-Pad141)") (class "Default")
      (node (ref "U1") (pin "141") (pinfunction "PE0_141") (pintype "bidirectional+no_connect"))
    )
    (net (code "108") (name "unconnected-(U1B-PE9-Pad60)") (class "Default")
      (node (ref "U1") (pin "60") (pinfunction "PE9_60") (pintype "bidirectional+no_connect"))
    )
    (net (code "109") (name "unconnected-(U1B-PE10-Pad63)") (class "Default")
      (node (ref "U1") (pin "63") (pinfunction "PE10_63") (pintype "bidirectional+no_connect"))
    )
    (net (code "110") (name "unconnected-(U1B-PE13-Pad66)") (class "Default")
      (node (ref "U1") (pin "66") (pinfunction "PE13_66") (pintype "bidirectional+no_connect"))
    )
    (net (code "111") (name "unconnected-(U1B-PE14-Pad67)") (class "Default")
      (node (ref "U1") (pin "67") (pinfunction "PE14_67") (pintype "bidirectional+no_connect"))
    )
    (net (code "112") (name "unconnected-(U1B-PE15-Pad68)") (class "Default")
      (node (ref "U1") (pin "68") (pinfunction "PE15_68") (pintype "bidirectional+no_connect"))
    )
    (net (code "113") (name "unconnected-(U1B-PF5-Pad15)") (class "Default")
      (node (ref "U1") (pin "15") (pinfunction "PF5_15") (pintype "bidirectional+no_connect"))
    )
    (net (code "114") (name "unconnected-(U1B-PF6-Pad18)") (class "Default")
      (node (ref "U1") (pin "18") (pinfunction "PF6_18") (pintype "bidirectional+no_connect"))
    )
    (net (code "115") (name "unconnected-(U1B-PF7-Pad19)") (class "Default")
      (node (ref "U1") (pin "19") (pinfunction "PF7_19") (pintype "bidirectional+no_connect"))
    )
    (net (code "116") (name "unconnected-(U1B-PF8-Pad20)") (class "Default")
      (node (ref "U1") (pin "20") (pinfunction "PF8_20") (pintype "bidirectional+no_connect"))
    )
    (net (code "117") (name "unconnected-(U1B-PF9-Pad21)") (class "Default")
      (node (ref "U1") (pin "21") (pinfunction "PF9_21") (pintype "bidirectional+no_connect"))
    )
    (net (code "118") (name "unconnected-(U1B-PF10-Pad22)") (class "Default")
      (node (ref "U1") (pin "22") (pinfunction "PF10_22") (pintype "bidirectional+no_connect"))
    )
    (net (code "119") (name "unconnected-(U1B-PF13-Pad53)") (class "Default")
      (node (ref "U1") (pin "53") (pinfunction "PF13_53") (pintype "bidirectional+no_connect"))
    )
    (net (code "120") (name "unconnected-(U1B-PF14-Pad54)") (class "Default")
      (node (ref "U1") (pin "54") (pinfunction "PF14_54") (pintype "bidirectional+no_connect"))
    )
    (net (code "121") (name "unconnected-(U1B-PF15-Pad55)") (class "Default")
      (node (ref "U1") (pin "55") (pinfunction "PF15_55") (pintype "bidirectional+no_connect"))
    )
    (net (code "122") (name "unconnected-(U1B-PG0-Pad56)") (class "Default")
      (node (ref "U1") (pin "56") (pinfunction "PG0_56") (pintype "bidirectional+no_connect"))
    )
    (net (code "123") (name "unconnected-(U1B-PG1-Pad57)") (class "Default")
      (node (ref "U1") (pin "57") (pinfunction "PG1_57") (pintype "bidirectional+no_connect"))
    )
    (net (code "124") (name "unconnected-(U1B-PG2-Pad87)") (class "Default")
      (node (ref "U1") (pin "87") (pinfunction "PG2_87") (pintype "bidirectional+no_connect"))
    )
    (net (code "125") (name "unconnected-(U1B-PG3-Pad88)") (class "Default")
      (node (ref "U1") (pin "88") (pinfunction "PG3_88") (pintype "bidirectional+no_connect"))
    )
    (net (code "126") (name "unconnected-(U1B-PG4-Pad89)") (class "Default")
      (node (ref "U1") (pin "89") (pinfunction "PG4_89") (pintype "bidirectional+no_connect"))
    )
    (net (code "127") (name "unconnected-(U1B-PG5-Pad90)") (class "Default")
      (node (ref "U1") (pin "90") (pinfunction "PG5_90") (pintype "bidirectional+no_connect"))
    )
    (net (code "128") (name "unconnected-(U1B-PG6-Pad91)") (class "Default")
      (node (ref "U1") (pin "91") (pinfunction "PG6_91") (pintype "bidirectional+no_connect"))
    )
    (net (code "129") (name "unconnected-(U1B-PG7-Pad92)") (class "Default")
      (node (ref "U1") (pin "92") (pinfunction "PG7_92") (pintype "bidirectional+no_connect"))
    )
    (net (code "130") (name "unconnected-(U1B-PG8-Pad93)") (class "Default")
      (node (ref "U1") (pin "93") (pinfunction "PG8_93") (pintype "bidirectional+no_connect"))
    )
    (net (code "131") (name "unconnected-(U1B-PG15-Pad132)") (class "Default")
      (node (ref "U1") (pin "132") (pinfunction "PG15_132") (pintype "bidirectional+no_connect"))
    )
    (net (code "132") (name "unconnected-(U1B-PH1-OSC_OUT(PH1)-Pad24)") (class "Default")
      (node (ref "U1") (pin "24") (pinfunction "PH1-OSC_OUT(PH1)_24") (pintype "bidirectional+no_connect"))
    )
  )
)
